# design.net
KiCad netlist of a schematic drawn in Altium Designer
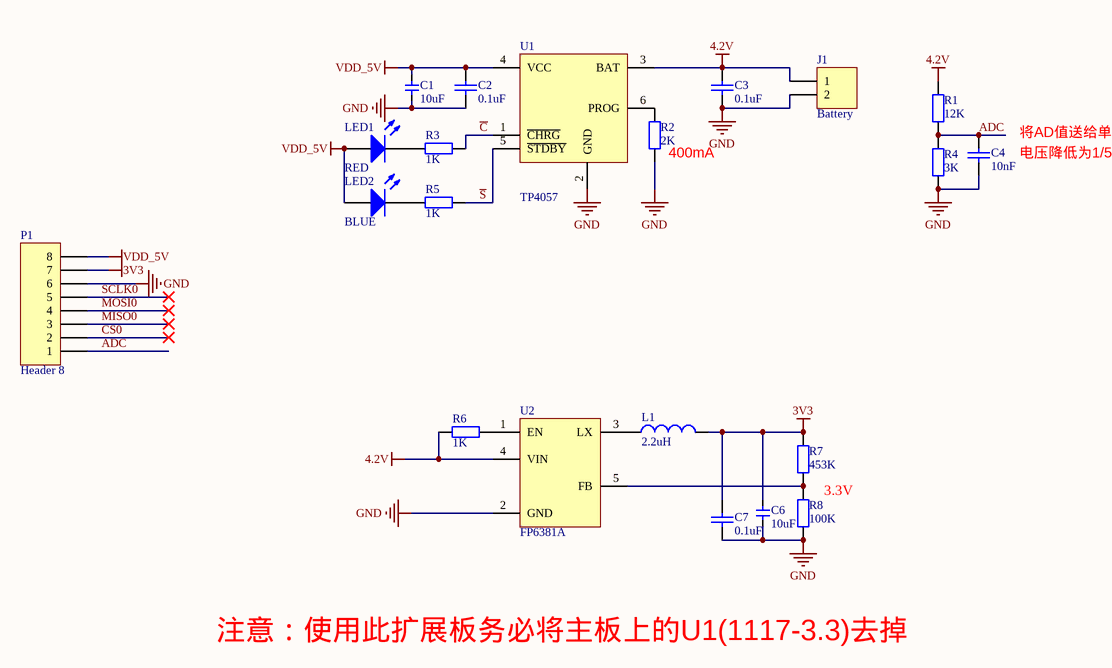
[diagram p0: 充电扩展板.SchDoc]

(export (version "E")
  (design (tool "Eeschema 10.0.6"))
  (components
    (comp (ref "C1")
      (value "10uF")
      (footprint "C_0603")
      (description "Capacitor")
      (libsource (lib "MyPcbLib") (part "电容-0402"))
    )
    (comp (ref "C2")
      (value "0.1uF")
      (footprint "C_0603")
      (description "Capacitor")
      (fields (field (name "PUBLISHER") "Altium Limited"))
      (libsource (lib "Miscellaneous Devices") (part "Cap"))
    )
    (comp (ref "C3")
      (value "0.1uF")
      (footprint "C_0603")
      (description "Capacitor")
      (fields (field (name "PUBLISHER") "Altium Limited"))
      (libsource (lib "Miscellaneous Devices") (part "Cap"))
    )
    (comp (ref "C4")
      (value "10nF")
      (footprint "C_0603")
      (description "Capacitor")
      (fields (field (name "PUBLISHER") "Altium Limited"))
      (libsource (lib "Miscellaneous Devices") (part "Cap"))
    )
    (comp (ref "C6")
      (value "10uF")
      (footprint "C_0603")
      (description "Capacitor")
      (libsource (lib "MyPcbLib") (part "电容-0402"))
    )
    (comp (ref "C7")
      (value "0.1uF")
      (footprint "C_0603")
      (description "Capacitor")
      (fields (field (name "PUBLISHER") "Altium Limited"))
      (libsource (lib "Miscellaneous Devices") (part "Cap"))
    )
    (comp (ref "J1")
      (value "Battery")
      (footprint "C_1812")
      (description "Header, 2-Pin")
      (fields (field (name "PUBLISHER") "Altium Limited"))
      (libsource (lib "Miscellaneous Connectors") (part "Header 2"))
    )
    (comp (ref "L1")
      (value "2.2uH")
      (footprint "CD32")
      (description "Inductor")
      (fields (field (name "PUBLISHER") "Altium Limited"))
      (libsource (lib "Miscellaneous Devices") (part "Inductor"))
    )
    (comp (ref "LED1")
      (value "RED")
      (footprint "0603/1608 LEDR")
      (description "Typical INFRARED GaAs LED")
      (fields (field (name "PUBLISHER") "Altium Limited"))
      (libsource (lib "Miscellaneous Devices") (part "LED0"))
    )
    (comp (ref "LED2")
      (value "BLUE")
      (footprint "0603/1608 LEDB")
      (description "Typical INFRARED GaAs LED")
      (fields (field (name "PUBLISHER") "Altium Limited"))
      (libsource (lib "Miscellaneous Devices") (part "LED0"))
    )
    (comp (ref "P1")
      (value "Header 8")
      (footprint "FFC_0.5_8")
      (description "Header, 8-Pin")
      (fields (field (name "PUBLISHER") "Altium Limited"))
      (libsource (lib "Miscellaneous Connectors") (part "Header 8"))
    )
    (comp (ref "R1")
      (value "12K")
      (footprint "R_0603")
      (description "Resistor")
      (fields (field (name "PUBLISHER") "Altium Limited"))
      (libsource (lib "") (part "Res2_1"))
    )
    (comp (ref "R2")
      (value "2K")
      (footprint "R_0603")
      (description "Resistor")
      (fields (field (name "PUBLISHER") "Altium Limited"))
      (libsource (lib "Miscellaneous Devices") (part "Res2"))
    )
    (comp (ref "R3")
      (value "1K")
      (footprint "R_0603")
      (description "Resistor")
      (fields (field (name "PUBLISHER") "Altium Limited"))
      (libsource (lib "Miscellaneous Devices") (part "Res2"))
    )
    (comp (ref "R4")
      (value "3K")
      (footprint "R_0603")
      (description "Resistor")
      (fields (field (name "PUBLISHER") "Altium Limited"))
      (libsource (lib "") (part "Res2_1"))
    )
    (comp (ref "R5")
      (value "1K")
      (footprint "R_0603")
      (description "Resistor")
      (fields (field (name "PUBLISHER") "Altium Limited"))
      (libsource (lib "Miscellaneous Devices") (part "Res2"))
    )
    (comp (ref "R6")
      (value "1K")
      (footprint "R_0603")
      (description "Resistor")
      (fields (field (name "PUBLISHER") "Altium Limited"))
      (libsource (lib "Miscellaneous Devices") (part "Res2"))
    )
    (comp (ref "R7")
      (value "453K")
      (footprint "R_0603")
      (description "Resistor")
      (fields (field (name "PUBLISHER") "Altium Limited"))
      (libsource (lib "") (part "Res2_1"))
    )
    (comp (ref "R8")
      (value "100K")
      (footprint "R_0603")
      (description "Resistor")
      (fields (field (name "PUBLISHER") "Altium Limited"))
      (libsource (lib "") (part "Res2_1"))
    )
    (comp (ref "U1")
      (value "TP4057")
      (footprint "SOT23-6-Y")
      (description "0.5A锂电池充电芯片")
      (libsource (lib "Misaka") (part "TP4057"))
    )
    (comp (ref "U2")
      (value "FP6381A")
      (footprint "SOT23-5-Y")
      (description "DC-DC  1.5MHz  1.2A")
      (libsource (lib "Misaka") (part "FP6381A"))
    )
  )
  (nets
    (net (code "1") (name "/ADC") (class "Default")
      (node (ref "C4") (pin "1") (pinfunction "1_1") (pintype "passive"))
      (node (ref "P1") (pin "1") (pinfunction "1_1") (pintype "passive"))
      (node (ref "R1") (pin "2") (pinfunction "2_2") (pintype "passive"))
      (node (ref "R4") (pin "1") (pinfunction "1_1") (pintype "passive"))
    )
    (net (code "2") (name "/CS0") (class "Default")
      (node (ref "P1") (pin "2") (pinfunction "2_2") (pintype "passive+no_connect"))
    )
    (net (code "3") (name "/MISO0") (class "Default")
      (node (ref "P1") (pin "3") (pinfunction "3_3") (pintype "passive+no_connect"))
    )
    (net (code "4") (name "/MOSI0") (class "Default")
      (node (ref "P1") (pin "4") (pinfunction "4_4") (pintype "passive+no_connect"))
    )
    (net (code "5") (name "/SCLK0") (class "Default")
      (node (ref "P1") (pin "5") (pinfunction "5_5") (pintype "passive+no_connect"))
    )
    (net (code "6") (name "/~{C}") (class "Default")
      (node (ref "R3") (pin "1") (pinfunction "1_1") (pintype "passive"))
      (node (ref "U1") (pin "1") (pinfunction "~{CHRG}_1") (pintype "passive"))
    )
    (net (code "7") (name "/~{S}") (class "Default")
      (node (ref "R5") (pin "1") (pinfunction "1_1") (pintype "passive"))
      (node (ref "U1") (pin "5") (pinfunction "~{STDBY}_5") (pintype "passive"))
    )
    (net (code "8") (name "3V3") (class "Default")
      (node (ref "C6") (pin "2") (pinfunction "2_2") (pintype "passive"))
      (node (ref "C7") (pin "1") (pinfunction "1_1") (pintype "passive"))
      (node (ref "L1") (pin "2") (pinfunction "2_2") (pintype "passive"))
      (node (ref "P1") (pin "7") (pinfunction "7_7") (pintype "passive"))
      (node (ref "R7") (pin "1") (pinfunction "1_1") (pintype "passive"))
    )
    (net (code "9") (name "4.2V") (class "Default")
      (node (ref "C3") (pin "1") (pinfunction "1_1") (pintype "passive"))
      (node (ref "J1") (pin "1") (pinfunction "1_1") (pintype "passive"))
      (node (ref "R1") (pin "1") (pinfunction "1_1") (pintype "passive"))
      (node (ref "R6") (pin "2") (pinfunction "2_2") (pintype "passive"))
      (node (ref "U1") (pin "3") (pinfunction "BAT_3") (pintype "passive"))
      (node (ref "U2") (pin "4") (pinfunction "VIN_4") (pintype "passive"))
    )
    (net (code "10") (name "GND") (class "Default")
      (node (ref "C1") (pin "1") (pinfunction "1_1") (pintype "passive"))
      (node (ref "C2") (pin "2") (pinfunction "2_2") (pintype "passive"))
      (node (ref "C3") (pin "2") (pinfunction "2_2") (pintype "passive"))
      (node (ref "C4") (pin "2") (pinfunction "2_2") (pintype "passive"))
      (node (ref "C6") (pin "1") (pinfunction "1_1") (pintype "passive"))
      (node (ref "C7") (pin "2") (pinfunction "2_2") (pintype "passive"))
      (node (ref "J1") (pin "2") (pinfunction "2_2") (pintype "passive"))
      (node (ref "P1") (pin "6") (pinfunction "6_6") (pintype "passive"))
      (node (ref "R2") (pin "2") (pinfunction "2_2") (pintype "passive"))
      (node (ref "R4") (pin "2") (pinfunction "2_2") (pintype "passive"))
      (node (ref "R8") (pin "2") (pinfunction "2_2") (pintype "passive"))
      (node (ref "U1") (pin "2") (pinfunction "GND_2") (pintype "passive"))
      (node (ref "U2") (pin "2") (pinfunction "GND_2") (pintype "passive"))
    )
    (net (code "11") (name "Net-(LED1-K)") (class "Default")
      (node (ref "LED1") (pin "2") (pinfunction "K_2") (pintype "passive"))
      (node (ref "R3") (pin "2") (pinfunction "2_2") (pintype "passive"))
    )
    (net (code "12") (name "Net-(LED2-K)") (class "Default")
      (node (ref "LED2") (pin "2") (pinfunction "K_2") (pintype "passive"))
      (node (ref "R5") (pin "2") (pinfunction "2_2") (pintype "passive"))
    )
    (net (code "13") (name "Net-(U1-PROG)") (class "Default")
      (node (ref "R2") (pin "1") (pinfunction "1_1") (pintype "passive"))
      (node (ref "U1") (pin "6") (pinfunction "PROG_6") (pintype "passive"))
    )
    (net (code "14") (name "Net-(U2-EN)") (class "Default")
      (node (ref "R6") (pin "1") (pinfunction "1_1") (pintype "passive"))
      (node (ref "U2") (pin "1") (pinfunction "EN_1") (pintype "passive"))
    )
    (net (code "15") (name "Net-(U2-FB)") (class "Default")
      (node (ref "R7") (pin "2") (pinfunction "2_2") (pintype "passive"))
      (node (ref "R8") (pin "1") (pinfunction "1_1") (pintype "passive"))
      (node (ref "U2") (pin "5") (pinfunction "FB_5") (pintype "passive"))
    )
    (net (code "16") (name "Net-(U2-LX)") (class "Default")
      (node (ref "L1") (pin "1") (pinfunction "1_1") (pintype "passive"))
      (node (ref "U2") (pin "3") (pinfunction "LX_3") (pintype "passive"))
    )
    (net (code "17") (name "VDD_5V") (class "Default")
      (node (ref "C1") (pin "2") (pinfunction "2_2") (pintype "passive"))
      (node (ref "C2") (pin "1") (pinfunction "1_1") (pintype "passive"))
      (node (ref "LED1") (pin "1") (pinfunction "A_1") (pintype "passive"))
      (node (ref "LED2") (pin "1") (pinfunction "A_1") (pintype "passive"))
      (node (ref "P1") (pin "8") (pinfunction "8_8") (pintype "passive"))
      (node (ref "U1") (pin "4") (pinfunction "VCC_4") (pintype "passive"))
    )
  )
)
